# amplifier_v0003_-_1_Channel_Test.net
KiCad netlist of a schematic drawn in EAGLE
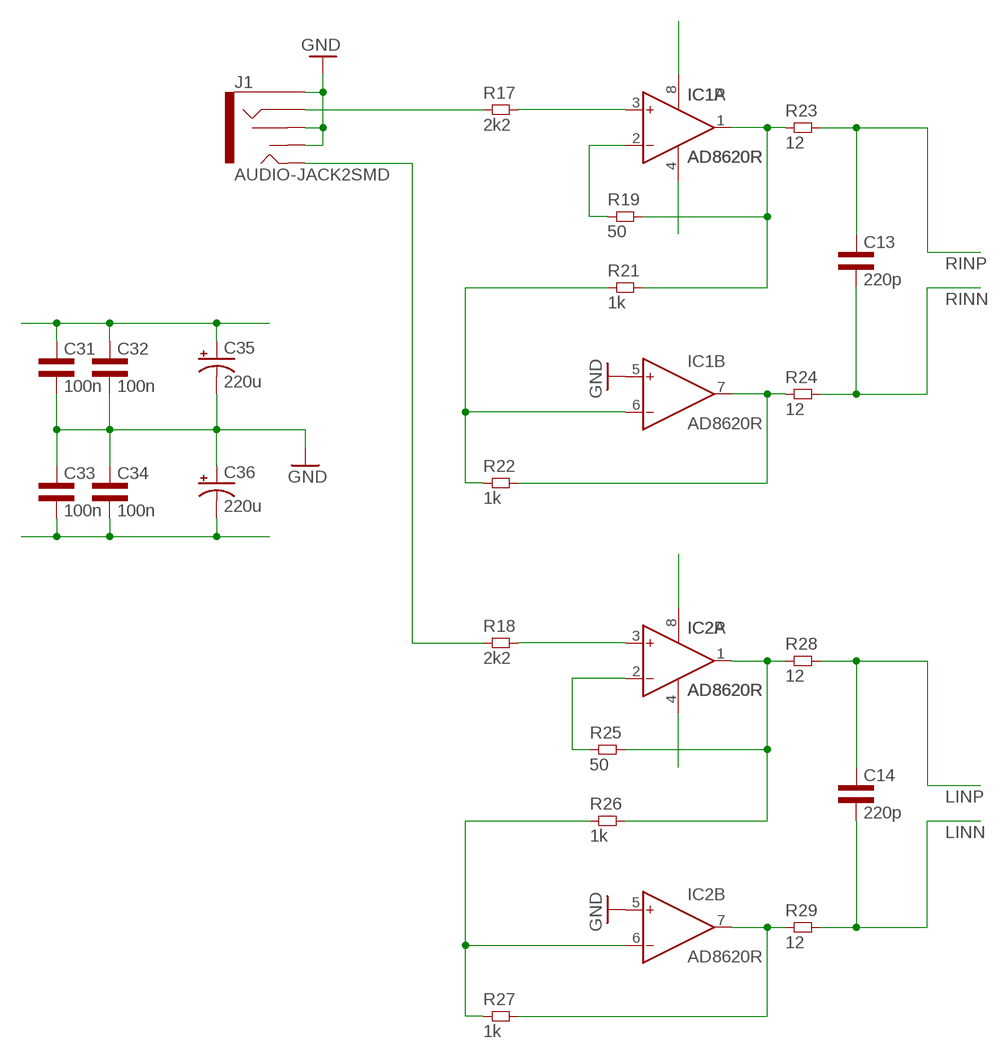
[diagram p0: schematic, sheet 1]
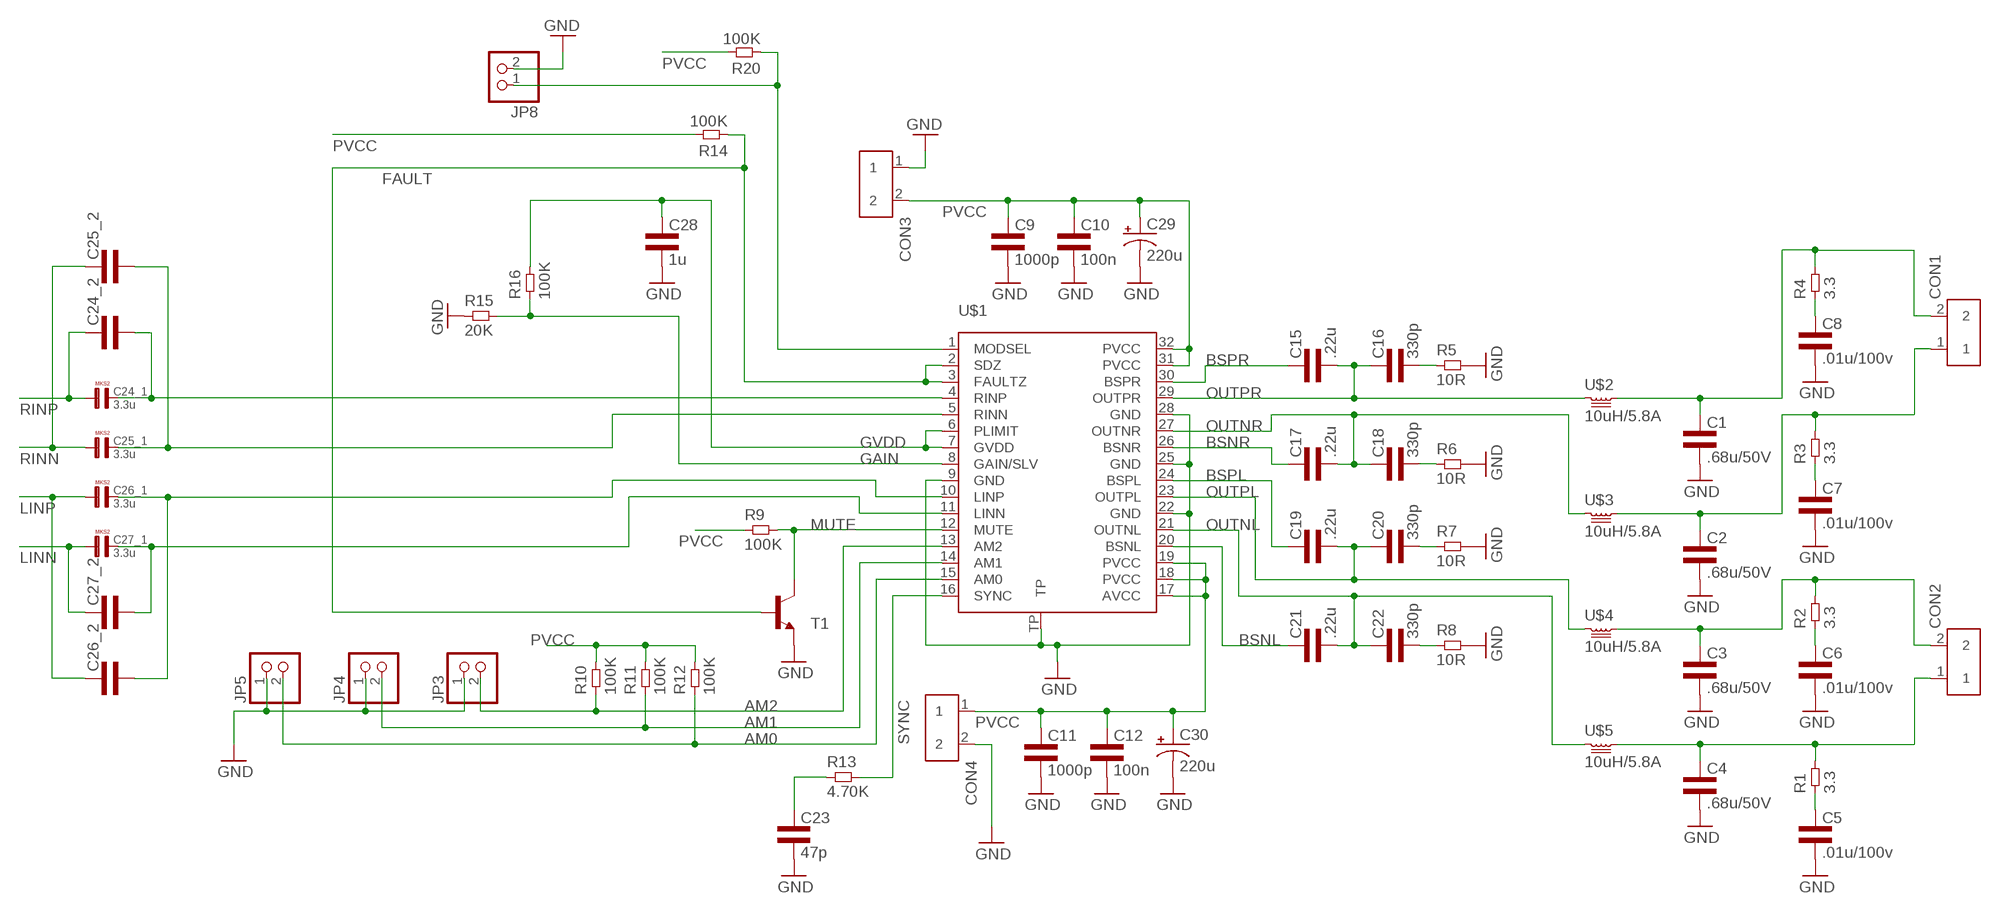
[diagram p1: schematic, sheet 2]

(export (version "E")
  (design (tool "Eeschema 10.0.6"))
  (components
    (comp (ref "C13")
      (value "220p")
      (footprint "eagle-import:0603L3")
      (libsource (lib "eagle-import") (part "CAP0603L3"))
    )
    (comp (ref "C14")
      (value "220p")
      (footprint "eagle-import:0603L3")
      (libsource (lib "eagle-import") (part "CAP0603L3"))
    )
    (comp (ref "C31")
      (value "100n")
      (footprint "eagle-import:0603L3")
      (libsource (lib "eagle-import") (part "CAP0603L3"))
    )
    (comp (ref "C32")
      (value "100n")
      (footprint "eagle-import:0603L3")
      (libsource (lib "eagle-import") (part "CAP0603L3"))
    )
    (comp (ref "C33")
      (value "100n")
      (footprint "eagle-import:0603L3")
      (libsource (lib "eagle-import") (part "CAP0603L3"))
    )
    (comp (ref "C34")
      (value "100n")
      (footprint "eagle-import:0603L3")
      (libsource (lib "eagle-import") (part "CAP0603L3"))
    )
    (comp (ref "C35")
      (value "220u")
      (footprint "eagle-import:CT7343")
      (libsource (lib "eagle-import") (part "CPOL-USCT7343"))
    )
    (comp (ref "C36")
      (value "220u")
      (footprint "eagle-import:CT7343")
      (libsource (lib "eagle-import") (part "CPOL-USCT7343"))
    )
    (comp (ref "IC1")
      (value "AD8620R")
      (footprint "eagle-import:SO8")
      (fields (field (name "MF") "ALTERA CORPORATION") (field (name "MPN") "AD8620ARZ"))
      (libsource (lib "eagle-import") (part "AD8620R"))
    )
    (comp (ref "IC2")
      (value "AD8620R")
      (footprint "eagle-import:SO8")
      (fields (field (name "MF") "ALTERA CORPORATION") (field (name "MPN") "AD8620ARZ"))
      (libsource (lib "eagle-import") (part "AD8620R"))
    )
    (comp (ref "J1")
      (value "AUDIO-JACK2SMD")
      (footprint "eagle-import:AUDIO-JACK-3.5MM-SMD")
      (libsource (lib "eagle-import") (part "AUDIO-JACK2SMD"))
    )
    (comp (ref "R17")
      (value "2k2")
      (footprint "eagle-import:0603L3")
      (libsource (lib "eagle-import") (part "RES0603L3"))
    )
    (comp (ref "R18")
      (value "2k2")
      (footprint "eagle-import:0603L3")
      (libsource (lib "eagle-import") (part "RES0603L3"))
    )
    (comp (ref "R19")
      (value "50")
      (footprint "eagle-import:0603L3")
      (libsource (lib "eagle-import") (part "RES0603L3"))
    )
    (comp (ref "R21")
      (value "1k")
      (footprint "eagle-import:0603L3")
      (libsource (lib "eagle-import") (part "RES0603L3"))
    )
    (comp (ref "R22")
      (value "1k")
      (footprint "eagle-import:0603L3")
      (libsource (lib "eagle-import") (part "RES0603L3"))
    )
    (comp (ref "R23")
      (value "12")
      (footprint "eagle-import:0603L3")
      (libsource (lib "eagle-import") (part "RES0603L3"))
    )
    (comp (ref "R24")
      (value "12")
      (footprint "eagle-import:0603L3")
      (libsource (lib "eagle-import") (part "RES0603L3"))
    )
    (comp (ref "R25")
      (value "50")
      (footprint "eagle-import:0603L3")
      (libsource (lib "eagle-import") (part "RES0603L3"))
    )
    (comp (ref "R26")
      (value "1k")
      (footprint "eagle-import:0603L3")
      (libsource (lib "eagle-import") (part "RES0603L3"))
    )
    (comp (ref "R27")
      (value "1k")
      (footprint "eagle-import:0603L3")
      (libsource (lib "eagle-import") (part "RES0603L3"))
    )
    (comp (ref "R28")
      (value "12")
      (footprint "eagle-import:0603L3")
      (libsource (lib "eagle-import") (part "RES0603L3"))
    )
    (comp (ref "R29")
      (value "12")
      (footprint "eagle-import:0603L3")
      (libsource (lib "eagle-import") (part "RES0603L3"))
    )
    (comp (ref "C1")
      (value ".68u/50V")
      (footprint "eagle-import:1206L3")
      (libsource (lib "eagle-import") (part "CAP1206L3"))
    )
    (comp (ref "C2")
      (value ".68u/50V")
      (footprint "eagle-import:1206L3")
      (libsource (lib "eagle-import") (part "CAP1206L3"))
    )
    (comp (ref "C3")
      (value ".68u/50V")
      (footprint "eagle-import:1206L3")
      (libsource (lib "eagle-import") (part "CAP1206L3"))
    )
    (comp (ref "C4")
      (value ".68u/50V")
      (footprint "eagle-import:1206L3")
      (libsource (lib "eagle-import") (part "CAP1206L3"))
    )
    (comp (ref "C5")
      (value ".01u/100v")
      (footprint "eagle-import:0805L3")
      (libsource (lib "eagle-import") (part "CAP0805L3"))
    )
    (comp (ref "C6")
      (value ".01u/100v")
      (footprint "eagle-import:0805L3")
      (libsource (lib "eagle-import") (part "CAP0805L3"))
    )
    (comp (ref "C7")
      (value ".01u/100v")
      (footprint "eagle-import:0805L3")
      (libsource (lib "eagle-import") (part "CAP0805L3"))
    )
    (comp (ref "C8")
      (value ".01u/100v")
      (footprint "eagle-import:0805L3")
      (libsource (lib "eagle-import") (part "CAP0805L3"))
    )
    (comp (ref "C9")
      (value "1000p")
      (footprint "eagle-import:0603L3")
      (libsource (lib "eagle-import") (part "CAP0603L3"))
    )
    (comp (ref "C10")
      (value "100n")
      (footprint "eagle-import:0603L3")
      (libsource (lib "eagle-import") (part "CAP0603L3"))
    )
    (comp (ref "C11")
      (value "1000p")
      (footprint "eagle-import:0603L3")
      (libsource (lib "eagle-import") (part "CAP0603L3"))
    )
    (comp (ref "C12")
      (value "100n")
      (footprint "eagle-import:0603L3")
      (libsource (lib "eagle-import") (part "CAP0603L3"))
    )
    (comp (ref "C15")
      (value ".22u")
      (footprint "eagle-import:0603L3")
      (libsource (lib "eagle-import") (part "CAP0603L3"))
    )
    (comp (ref "C16")
      (value "330p")
      (footprint "eagle-import:0603L3")
      (libsource (lib "eagle-import") (part "CAP0603L3"))
    )
    (comp (ref "C17")
      (value ".22u")
      (footprint "eagle-import:0603L3")
      (libsource (lib "eagle-import") (part "CAP0603L3"))
    )
    (comp (ref "C18")
      (value "330p")
      (footprint "eagle-import:0603L3")
      (libsource (lib "eagle-import") (part "CAP0603L3"))
    )
    (comp (ref "C19")
      (value ".22u")
      (footprint "eagle-import:0603L3")
      (libsource (lib "eagle-import") (part "CAP0603L3"))
    )
    (comp (ref "C20")
      (value "330p")
      (footprint "eagle-import:0603L3")
      (libsource (lib "eagle-import") (part "CAP0603L3"))
    )
    (comp (ref "C21")
      (value ".22u")
      (footprint "eagle-import:0603L3")
      (libsource (lib "eagle-import") (part "CAP0603L3"))
    )
    (comp (ref "C22")
      (value "330p")
      (footprint "eagle-import:0603L3")
      (libsource (lib "eagle-import") (part "CAP0603L3"))
    )
    (comp (ref "C23")
      (value "47p")
      (footprint "eagle-import:0603L3")
      (libsource (lib "eagle-import") (part "CAP0603L3"))
    )
    (comp (ref "C24_1")
      (value "3.3u")
      (footprint "eagle-import:R5B5K5")
      (libsource (lib "eagle-import") (part "3,3µF"))
    )
    (comp (ref "C24_2")
      (value "CAP1206L3")
      (footprint "eagle-import:1206L3")
      (libsource (lib "eagle-import") (part "CAP1206L3"))
    )
    (comp (ref "C25_1")
      (value "3.3u")
      (footprint "eagle-import:R5B5K5")
      (libsource (lib "eagle-import") (part "3,3µF"))
    )
    (comp (ref "C25_2")
      (value "CAP1206L3")
      (footprint "eagle-import:1206L3")
      (libsource (lib "eagle-import") (part "CAP1206L3"))
    )
    (comp (ref "C26_1")
      (value "3.3u")
      (footprint "eagle-import:R5B5K5")
      (libsource (lib "eagle-import") (part "3,3µF"))
    )
    (comp (ref "C26_2")
      (value "CAP1206L3")
      (footprint "eagle-import:1206L3")
      (libsource (lib "eagle-import") (part "CAP1206L3"))
    )
    (comp (ref "C27_1")
      (value "3.3u")
      (footprint "eagle-import:R5B5K5")
      (libsource (lib "eagle-import") (part "3,3µF"))
    )
    (comp (ref "C27_2")
      (value "CAP1206L3")
      (footprint "eagle-import:1206L3")
      (libsource (lib "eagle-import") (part "CAP1206L3"))
    )
    (comp (ref "C28")
      (value "1u")
      (footprint "eagle-import:0603L3")
      (libsource (lib "eagle-import") (part "CAP0603L3"))
    )
    (comp (ref "C29")
      (value "220u")
      (footprint "eagle-import:PANASONIC_G")
      (libsource (lib "eagle-import") (part "CPOL-USG"))
    )
    (comp (ref "C30")
      (value "220u")
      (footprint "eagle-import:PANASONIC_G")
      (libsource (lib "eagle-import") (part "CPOL-USG"))
    )
    (comp (ref "CON1")
      (value "TERM_BLOCK_2")
      (footprint "eagle-import:TERM_BLOCK_2")
      (libsource (lib "eagle-import") (part "TERM_BLOCK_2"))
    )
    (comp (ref "CON2")
      (value "TERM_BLOCK_2")
      (footprint "eagle-import:TERM_BLOCK_2")
      (libsource (lib "eagle-import") (part "TERM_BLOCK_2"))
    )
    (comp (ref "CON3")
      (value "TERM_BLOCK_2")
      (footprint "eagle-import:TERM_BLOCK_2")
      (libsource (lib "eagle-import") (part "TERM_BLOCK_2"))
    )
    (comp (ref "CON4")
      (value "TERM_BLOCK_2")
      (footprint "eagle-import:TERM_BLOCK_2")
      (libsource (lib "eagle-import") (part "TERM_BLOCK_2"))
    )
    (comp (ref "JP3")
      (value "PINHD-1X2")
      (footprint "eagle-import:1X02")
      (libsource (lib "eagle-import") (part "PINHD-1X2"))
    )
    (comp (ref "JP4")
      (value "PINHD-1X2")
      (footprint "eagle-import:1X02")
      (libsource (lib "eagle-import") (part "PINHD-1X2"))
    )
    (comp (ref "JP5")
      (value "PINHD-1X2")
      (footprint "eagle-import:1X02")
      (libsource (lib "eagle-import") (part "PINHD-1X2"))
    )
    (comp (ref "JP8")
      (value "PINHD-1X2")
      (footprint "eagle-import:1X02")
      (libsource (lib "eagle-import") (part "PINHD-1X2"))
    )
    (comp (ref "R1")
      (value "3.3")
      (footprint "eagle-import:0603L3")
      (libsource (lib "eagle-import") (part "RES0603L3"))
    )
    (comp (ref "R2")
      (value "3.3")
      (footprint "eagle-import:0603L3")
      (libsource (lib "eagle-import") (part "RES0603L3"))
    )
    (comp (ref "R3")
      (value "3.3")
      (footprint "eagle-import:0603L3")
      (libsource (lib "eagle-import") (part "RES0603L3"))
    )
    (comp (ref "R4")
      (value "3.3")
      (footprint "eagle-import:0603L3")
      (libsource (lib "eagle-import") (part "RES0603L3"))
    )
    (comp (ref "R5")
      (value "10R")
      (footprint "eagle-import:1206L3")
      (libsource (lib "eagle-import") (part "RES1206L3"))
    )
    (comp (ref "R6")
      (value "10R")
      (footprint "eagle-import:1206L3")
      (libsource (lib "eagle-import") (part "RES1206L3"))
    )
    (comp (ref "R7")
      (value "10R")
      (footprint "eagle-import:1206L3")
      (libsource (lib "eagle-import") (part "RES1206L3"))
    )
    (comp (ref "R8")
      (value "10R")
      (footprint "eagle-import:1206L3")
      (libsource (lib "eagle-import") (part "RES1206L3"))
    )
    (comp (ref "R9")
      (value "100K")
      (footprint "eagle-import:0603L3")
      (libsource (lib "eagle-import") (part "RES0603L3"))
    )
    (comp (ref "R10")
      (value "100K")
      (footprint "eagle-import:0603L3")
      (libsource (lib "eagle-import") (part "RES0603L3"))
    )
    (comp (ref "R11")
      (value "100K")
      (footprint "eagle-import:0603L3")
      (libsource (lib "eagle-import") (part "RES0603L3"))
    )
    (comp (ref "R12")
      (value "100K")
      (footprint "eagle-import:0603L3")
      (libsource (lib "eagle-import") (part "RES0603L3"))
    )
    (comp (ref "R13")
      (value "4.70K")
      (footprint "eagle-import:0603L3")
      (libsource (lib "eagle-import") (part "RES0603L3"))
    )
    (comp (ref "R14")
      (value "100K")
      (footprint "eagle-import:0603L3")
      (libsource (lib "eagle-import") (part "RES0603L3"))
    )
    (comp (ref "R15")
      (value "20K")
      (footprint "eagle-import:0603L3")
      (libsource (lib "eagle-import") (part "RES0603L3"))
    )
    (comp (ref "R16")
      (value "100K")
      (footprint "eagle-import:0603L3")
      (libsource (lib "eagle-import") (part "RES0603L3"))
    )
    (comp (ref "R20")
      (value "100K")
      (footprint "eagle-import:0603L3")
      (libsource (lib "eagle-import") (part "RES0603L3"))
    )
    (comp (ref "T1")
      (value "TRANSISTOR_MMBT2222ALT1-NPN-SOT23-BEC")
      (footprint "eagle-import:TRANSISTOR_SOT23-BEC")
      (libsource (lib "eagle-import") (part "TRANSISTOR_-NPN-SOT23-BECMMBT2222ALT1"))
    )
    (comp (ref "U$1")
      (value "TPA3116")
      (footprint "eagle-import:R-PDSO-32")
      (libsource (lib "eagle-import") (part "TPA3116"))
    )
    (comp (ref "U$2")
      (value "10uH/5.8A")
      (footprint "eagle-import:DR127")
      (libsource (lib "eagle-import") (part "INDUCTORDR127"))
    )
    (comp (ref "U$3")
      (value "10uH/5.8A")
      (footprint "eagle-import:DR127")
      (libsource (lib "eagle-import") (part "INDUCTORDR127"))
    )
    (comp (ref "U$4")
      (value "10uH/5.8A")
      (footprint "eagle-import:DR127")
      (libsource (lib "eagle-import") (part "INDUCTORDR127"))
    )
    (comp (ref "U$5")
      (value "10uH/5.8A")
      (footprint "eagle-import:DR127")
      (libsource (lib "eagle-import") (part "INDUCTORDR127"))
    )
  )
  (nets
    (net (code "1") (name "AM0") (class "Default")
      (node (ref "JP5") (pin "2") (pinfunction "2_2") (pintype "passive"))
      (node (ref "R12") (pin "P$1") (pinfunction "1_P$1") (pintype "bidirectional"))
      (node (ref "U$1") (pin "15") (pinfunction "AM0_15") (pintype "bidirectional"))
    )
    (net (code "2") (name "AM1") (class "Default")
      (node (ref "JP4") (pin "2") (pinfunction "2_2") (pintype "passive"))
      (node (ref "R11") (pin "P$1") (pinfunction "1_P$1") (pintype "bidirectional"))
      (node (ref "U$1") (pin "14") (pinfunction "AM1_14") (pintype "bidirectional"))
    )
    (net (code "3") (name "AM2") (class "Default")
      (node (ref "JP3") (pin "2") (pinfunction "2_2") (pintype "passive"))
      (node (ref "R10") (pin "P$1") (pinfunction "1_P$1") (pintype "bidirectional"))
      (node (ref "U$1") (pin "13") (pinfunction "AM2_13") (pintype "bidirectional"))
    )
    (net (code "4") (name "BSNL") (class "Default")
      (node (ref "C21") (pin "P$1") (pinfunction "1_P$1") (pintype "bidirectional"))
      (node (ref "U$1") (pin "20") (pinfunction "BSNL_20") (pintype "bidirectional"))
    )
    (net (code "5") (name "BSNR") (class "Default")
      (node (ref "C17") (pin "P$1") (pinfunction "1_P$1") (pintype "bidirectional"))
      (node (ref "U$1") (pin "26") (pinfunction "BSNR_26") (pintype "bidirectional"))
    )
    (net (code "6") (name "BSPL") (class "Default")
      (node (ref "C19") (pin "P$1") (pinfunction "1_P$1") (pintype "bidirectional"))
      (node (ref "U$1") (pin "24") (pinfunction "BSPL_24") (pintype "bidirectional"))
    )
    (net (code "7") (name "BSPR") (class "Default")
      (node (ref "C15") (pin "P$1") (pinfunction "1_P$1") (pintype "bidirectional"))
      (node (ref "U$1") (pin "30") (pinfunction "BSPR_30") (pintype "bidirectional"))
    )
    (net (code "8") (name "FAULT") (class "Default")
      (node (ref "R14") (pin "P$1") (pinfunction "1_P$1") (pintype "bidirectional"))
      (node (ref "T1") (pin "B") (pinfunction "B_B") (pintype "passive"))
      (node (ref "U$1") (pin "2") (pinfunction "SDZ_2") (pintype "bidirectional"))
      (node (ref "U$1") (pin "3") (pinfunction "FAULTZ_3") (pintype "bidirectional"))
    )
    (net (code "9") (name "GAIN") (class "Default")
      (node (ref "R15") (pin "P$2") (pinfunction "2_P$2") (pintype "bidirectional"))
      (node (ref "R16") (pin "P$1") (pinfunction "1_P$1") (pintype "bidirectional"))
      (node (ref "U$1") (pin "8") (pinfunction "GAIN/SLV_8") (pintype "bidirectional"))
    )
    (net (code "10") (name "GND") (class "Default")
      (node (ref "C1") (pin "2") (pinfunction "2_2") (pintype "bidirectional"))
      (node (ref "C10") (pin "P$2") (pinfunction "2_P$2") (pintype "bidirectional"))
      (node (ref "C11") (pin "P$2") (pinfunction "2_P$2") (pintype "bidirectional"))
      (node (ref "C12") (pin "P$2") (pinfunction "2_P$2") (pintype "bidirectional"))
      (node (ref "C2") (pin "2") (pinfunction "2_2") (pintype "bidirectional"))
      (node (ref "C23") (pin "P$2") (pinfunction "2_P$2") (pintype "bidirectional"))
      (node (ref "C28") (pin "P$2") (pinfunction "2_P$2") (pintype "bidirectional"))
      (node (ref "C29") (pin "-") (pinfunction "-_-") (pintype "passive"))
      (node (ref "C3") (pin "2") (pinfunction "2_2") (pintype "bidirectional"))
      (node (ref "C30") (pin "-") (pinfunction "-_-") (pintype "passive"))
      (node (ref "C31") (pin "P$2") (pinfunction "2_P$2") (pintype "bidirectional"))
      (node (ref "C32") (pin "P$2") (pinfunction "2_P$2") (pintype "bidirectional"))
      (node (ref "C33") (pin "P$1") (pinfunction "1_P$1") (pintype "bidirectional"))
      (node (ref "C34") (pin "P$1") (pinfunction "1_P$1") (pintype "bidirectional"))
      (node (ref "C35") (pin "-") (pinfunction "-_-") (pintype "passive"))
      (node (ref "C36") (pin "+") (pinfunction "+_+") (pintype "passive"))
      (node (ref "C4") (pin "2") (pinfunction "2_2") (pintype "bidirectional"))
      (node (ref "C5") (pin "2") (pinfunction "2_2") (pintype "bidirectional"))
      (node (ref "C6") (pin "2") (pinfunction "2_2") (pintype "bidirectional"))
      (node (ref "C7") (pin "2") (pinfunction "2_2") (pintype "bidirectional"))
      (node (ref "C8") (pin "2") (pinfunction "2_2") (pintype "bidirectional"))
      (node (ref "C9") (pin "P$2") (pinfunction "2_P$2") (pintype "bidirectional"))
      (node (ref "CON3") (pin "1") (pinfunction "1_1") (pintype "bidirectional"))
      (node (ref "CON4") (pin "2") (pinfunction "2_2") (pintype "bidirectional"))
      (node (ref "IC1") (pin "5") (pinfunction "IN+_5") (pintype "input"))
      (node (ref "IC2") (pin "5") (pinfunction "IN+_5") (pintype "input"))
      (node (ref "J1") (pin "RSH") (pinfunction "RSH_RSH") (pintype "bidirectional"))
      (node (ref "J1") (pin "SLEEVE") (pinfunction "SLEEVE_SLEEVE") (pintype "bidirectional"))
      (node (ref "J1") (pin "TSH") (pinfunction "TSH_TSH") (pintype "bidirectional"))
      (node (ref "JP3") (pin "1") (pinfunction "1_1") (pintype "passive"))
      (node (ref "JP4") (pin "1") (pinfunction "1_1") (pintype "passive"))
      (node (ref "JP5") (pin "1") (pinfunction "1_1") (pintype "passive"))
      (node (ref "JP8") (pin "2") (pinfunction "2_2") (pintype "passive"))
      (node (ref "R15") (pin "P$1") (pinfunction "1_P$1") (pintype "bidirectional"))
      (node (ref "R5") (pin "2") (pinfunction "2_2") (pintype "bidirectional"))
      (node (ref "R6") (pin "2") (pinfunction "2_2") (pintype "bidirectional"))
      (node (ref "R7") (pin "2") (pinfunction "2_2") (pintype "bidirectional"))
      (node (ref "R8") (pin "2") (pinfunction "2_2") (pintype "bidirectional"))
      (node (ref "T1") (pin "E") (pinfunction "E_E") (pintype "passive"))
      (node (ref "U$1") (pin "22") (pinfunction "GND_22") (pintype "bidirectional"))
      (node (ref "U$1") (pin "25") (pinfunction "GND_25") (pintype "bidirectional"))
      (node (ref "U$1") (pin "28") (pinfunction "GND_28") (pintype "bidirectional"))
      (node (ref "U$1") (pin "9") (pinfunction "GND_9") (pintype "bidirectional"))
      (node (ref "U$1") (pin "TP") (pinfunction "TP_TP") (pintype "bidirectional"))
    )
    (net (code "11") (name "GVDD") (class "Default")
      (node (ref "C28") (pin "P$1") (pinfunction "1_P$1") (pintype "bidirectional"))
      (node (ref "R16") (pin "P$2") (pinfunction "2_P$2") (pintype "bidirectional"))
      (node (ref "U$1") (pin "6") (pinfunction "PLIMIT_6") (pintype "bidirectional"))
      (node (ref "U$1") (pin "7") (pinfunction "GVDD_7") (pintype "bidirectional"))
    )
    (net (code "12") (name "LINN") (class "Default")
      (node (ref "C14") (pin "P$2") (pinfunction "2_P$2") (pintype "bidirectional"))
      (node (ref "C27_1") (pin "1") (pinfunction "1_1") (pintype "passive"))
      (node (ref "C27_2") (pin "1") (pinfunction "1_1") (pintype "bidirectional"))
      (node (ref "R29") (pin "P$2") (pinfunction "2_P$2") (pintype "bidirectional"))
    )
    (net (code "13") (name "LINP") (class "Default")
      (node (ref "C14") (pin "P$1") (pinfunction "1_P$1") (pintype "bidirectional"))
      (node (ref "C26_1") (pin "1") (pinfunction "1_1") (pintype "passive"))
      (node (ref "C26_2") (pin "1") (pinfunction "1_1") (pintype "bidirectional"))
      (node (ref "R28") (pin "P$2") (pinfunction "2_P$2") (pintype "bidirectional"))
    )
    (net (code "14") (name "MUTE") (class "Default")
      (node (ref "R9") (pin "P$2") (pinfunction "2_P$2") (pintype "bidirectional"))
      (node (ref "T1") (pin "C") (pinfunction "C_C") (pintype "passive"))
      (node (ref "U$1") (pin "12") (pinfunction "MUTE_12") (pintype "bidirectional"))
    )
    (net (code "15") (name "Net-(C16-2)") (class "Default")
      (node (ref "C16") (pin "P$2") (pinfunction "2_P$2") (pintype "bidirectional"))
      (node (ref "R5") (pin "1") (pinfunction "1_1") (pintype "bidirectional"))
    )
    (net (code "16") (name "Net-(C18-2)") (class "Default")
      (node (ref "C18") (pin "P$2") (pinfunction "2_P$2") (pintype "bidirectional"))
      (node (ref "R6") (pin "1") (pinfunction "1_1") (pintype "bidirectional"))
    )
    (net (code "17") (name "Net-(C20-2)") (class "Default")
      (node (ref "C20") (pin "P$2") (pinfunction "2_P$2") (pintype "bidirectional"))
      (node (ref "R7") (pin "1") (pinfunction "1_1") (pintype "bidirectional"))
    )
    (net (code "18") (name "Net-(C22-2)") (class "Default")
      (node (ref "C22") (pin "P$2") (pinfunction "2_P$2") (pintype "bidirectional"))
      (node (ref "R8") (pin "1") (pinfunction "1_1") (pintype "bidirectional"))
    )
    (net (code "19") (name "Net-(C23-1)") (class "Default")
      (node (ref "C23") (pin "P$1") (pinfunction "1_P$1") (pintype "bidirectional"))
      (node (ref "R13") (pin "P$1") (pinfunction "1_P$1") (pintype "bidirectional"))
    )
    (net (code "20") (name "Net-(IC1A-IN+)") (class "Default")
      (node (ref "IC1") (pin "3") (pinfunction "IN+_3") (pintype "input"))
      (node (ref "R17") (pin "P$2") (pinfunction "2_P$2") (pintype "bidirectional"))
    )
    (net (code "21") (name "Net-(IC1A-IN-)") (class "Default")
      (node (ref "IC1") (pin "2") (pinfunction "IN-_2") (pintype "input"))
      (node (ref "R19") (pin "P$1") (pinfunction "1_P$1") (pintype "bidirectional"))
    )
    (net (code "22") (name "Net-(IC1A-OUT)") (class "Default")
      (node (ref "IC1") (pin "1") (pinfunction "OUT_1") (pintype "output"))
      (node (ref "R19") (pin "P$2") (pinfunction "2_P$2") (pintype "bidirectional"))
      (node (ref "R21") (pin "P$2") (pinfunction "2_P$2") (pintype "bidirectional"))
      (node (ref "R23") (pin "P$1") (pinfunction "1_P$1") (pintype "bidirectional"))
    )
    (net (code "23") (name "Net-(IC1B-IN-)") (class "Default")
      (node (ref "IC1") (pin "6") (pinfunction "IN-_6") (pintype "input"))
      (node (ref "R21") (pin "P$1") (pinfunction "1_P$1") (pintype "bidirectional"))
      (node (ref "R22") (pin "P$1") (pinfunction "1_P$1") (pintype "bidirectional"))
    )
    (net (code "24") (name "Net-(IC1B-OUT)") (class "Default")
      (node (ref "IC1") (pin "7") (pinfunction "OUT_7") (pintype "output"))
      (node (ref "R22") (pin "P$2") (pinfunction "2_P$2") (pintype "bidirectional"))
      (node (ref "R24") (pin "P$1") (pinfunction "1_P$1") (pintype "bidirectional"))
    )
    (net (code "25") (name "Net-(IC2A-IN+)") (class "Default")
      (node (ref "IC2") (pin "3") (pinfunction "IN+_3") (pintype "input"))
      (node (ref "R18") (pin "P$2") (pinfunction "2_P$2") (pintype "bidirectional"))
    )
    (net (code "26") (name "Net-(IC2A-IN-)") (class "Default")
      (node (ref "IC2") (pin "2") (pinfunction "IN-_2") (pintype "input"))
      (node (ref "R25") (pin "P$1") (pinfunction "1_P$1") (pintype "bidirectional"))
    )
    (net (code "27") (name "Net-(IC2A-OUT)") (class "Default")
      (node (ref "IC2") (pin "1") (pinfunction "OUT_1") (pintype "output"))
      (node (ref "R25") (pin "P$2") (pinfunction "2_P$2") (pintype "bidirectional"))
      (node (ref "R26") (pin "P$2") (pinfunction "2_P$2") (pintype "bidirectional"))
      (node (ref "R28") (pin "P$1") (pinfunction "1_P$1") (pintype "bidirectional"))
    )
    (net (code "28") (name "Net-(IC2B-IN-)") (class "Default")
      (node (ref "IC2") (pin "6") (pinfunction "IN-_6") (pintype "input"))
      (node (ref "R26") (pin "P$1") (pinfunction "1_P$1") (pintype "bidirectional"))
      (node (ref "R27") (pin "P$1") (pinfunction "1_P$1") (pintype "bidirectional"))
    )
    (net (code "29") (name "Net-(IC2B-OUT)") (class "Default")
      (node (ref "IC2") (pin "7") (pinfunction "OUT_7") (pintype "output"))
      (node (ref "R27") (pin "P$2") (pinfunction "2_P$2") (pintype "bidirectional"))
      (node (ref "R29") (pin "P$1") (pinfunction "1_P$1") (pintype "bidirectional"))
    )
    (net (code "30") (name "Net-(R1-1)") (class "Default")
      (node (ref "C5") (pin "1") (pinfunction "1_1") (pintype "bidirectional"))
      (node (ref "R1") (pin "P$1") (pinfunction "1_P$1") (pintype "bidirectional"))
    )
    (net (code "31") (name "Net-(R1-2)") (class "Default")
      (node (ref "C4") (pin "1") (pinfunction "1_1") (pintype "bidirectional"))
      (node (ref "CON2") (pin "1") (pinfunction "1_1") (pintype "bidirectional"))
      (node (ref "R1") (pin "P$2") (pinfunction "2_P$2") (pintype "bidirectional"))
      (node (ref "U$5") (pin "2") (pinfunction "2_2") (pintype "bidirectional"))
    )
    (net (code "32") (name "Net-(R2-1)") (class "Default")
      (node (ref "C6") (pin "1") (pinfunction "1_1") (pintype "bidirectional"))
      (node (ref "R2") (pin "P$1") (pinfunction "1_P$1") (pintype "bidirectional"))
    )
    (net (code "33") (name "Net-(R2-2)") (class "Default")
      (node (ref "C3") (pin "1") (pinfunction "1_1") (pintype "bidirectional"))
      (node (ref "CON2") (pin "2") (pinfunction "2_2") (pintype "bidirectional"))
      (node (ref "R2") (pin "P$2") (pinfunction "2_P$2") (pintype "bidirectional"))
      (node (ref "U$4") (pin "2") (pinfunction "2_2") (pintype "bidirectional"))
    )
    (net (code "34") (name "Net-(R3-1)") (class "Default")
      (node (ref "C7") (pin "1") (pinfunction "1_1") (pintype "bidirectional"))
      (node (ref "R3") (pin "P$1") (pinfunction "1_P$1") (pintype "bidirectional"))
    )
    (net (code "35") (name "Net-(R3-2)") (class "Default")
      (node (ref "C2") (pin "1") (pinfunction "1_1") (pintype "bidirectional"))
      (node (ref "CON1") (pin "1") (pinfunction "1_1") (pintype "bidirectional"))
      (node (ref "R3") (pin "P$2") (pinfunction "2_P$2") (pintype "bidirectional"))
      (node (ref "U$3") (pin "2") (pinfunction "2_2") (pintype "bidirectional"))
    )
    (net (code "36") (name "Net-(R4-1)") (class "Default")
      (node (ref "C8") (pin "1") (pinfunction "1_1") (pintype "bidirectional"))
      (node (ref "R4") (pin "P$1") (pinfunction "1_P$1") (pintype "bidirectional"))
    )
    (net (code "37") (name "Net-(R4-2)") (class "Default")
      (node (ref "C1") (pin "1") (pinfunction "1_1") (pintype "bidirectional"))
      (node (ref "CON1") (pin "2") (pinfunction "2_2") (pintype "bidirectional"))
      (node (ref "R4") (pin "P$2") (pinfunction "2_P$2") (pintype "bidirectional"))
      (node (ref "U$2") (pin "2") (pinfunction "2_2") (pintype "bidirectional"))
    )
    (net (code "38") (name "Net-(R17-1)") (class "Default")
      (node (ref "J1") (pin "RING") (pinfunction "RING_RING") (pintype "bidirectional"))
      (node (ref "R17") (pin "P$1") (pinfunction "1_P$1") (pintype "bidirectional"))
    )
    (net (code "39") (name "Net-(R18-1)") (class "Default")
      (node (ref "J1") (pin "TIP") (pinfunction "TIP_TIP") (pintype "bidirectional"))
      (node (ref "R18") (pin "P$1") (pinfunction "1_P$1") (pintype "bidirectional"))
    )
    (net (code "40") (name "Net-(R20-1)") (class "Default")
      (node (ref "JP8") (pin "1") (pinfunction "1_1") (pintype "passive"))
      (node (ref "R20") (pin "P$1") (pinfunction "1_P$1") (pintype "bidirectional"))
      (node (ref "U$1") (pin "1") (pinfunction "MODSEL_1") (pintype "bidirectional"))
    )
    (net (code "41") (name "Net-(U$1-LINN)") (class "Default")
      (node (ref "C27_1") (pin "2") (pinfunction "2_2") (pintype "passive"))
      (node (ref "C27_2") (pin "2") (pinfunction "2_2") (pintype "bidirectional"))
      (node (ref "U$1") (pin "11") (pinfunction "LINN_11") (pintype "bidirectional"))
    )
    (net (code "42") (name "Net-(U$1-LINP)") (class "Default")
      (node (ref "C26_1") (pin "2") (pinfunction "2_2") (pintype "passive"))
      (node (ref "C26_2") (pin "2") (pinfunction "2_2") (pintype "bidirectional"))
      (node (ref "U$1") (pin "10") (pinfunction "LINP_10") (pintype "bidirectional"))
    )
    (net (code "43") (name "Net-(U$1-RINN)") (class "Default")
      (node (ref "C25_1") (pin "2") (pinfunction "2_2") (pintype "passive"))
      (node (ref "C25_2") (pin "2") (pinfunction "2_2") (pintype "bidirectional"))
      (node (ref "U$1") (pin "5") (pinfunction "RINN_5") (pintype "bidirectional"))
    )
    (net (code "44") (name "Net-(U$1-RINP)") (class "Default")
      (node (ref "C24_1") (pin "2") (pinfunction "2_2") (pintype "passive"))
      (node (ref "C24_2") (pin "2") (pinfunction "2_2") (pintype "bidirectional"))
      (node (ref "U$1") (pin "4") (pinfunction "RINP_4") (pintype "bidirectional"))
    )
    (net (code "45") (name "OUTNL") (class "Default")
      (node (ref "C21") (pin "P$2") (pinfunction "2_P$2") (pintype "bidirectional"))
      (node (ref "C22") (pin "P$1") (pinfunction "1_P$1") (pintype "bidirectional"))
      (node (ref "U$1") (pin "21") (pinfunction "OUTNL_21") (pintype "bidirectional"))
      (node (ref "U$5") (pin "1") (pinfunction "1_1") (pintype "bidirectional"))
    )
    (net (code "46") (name "OUTNR") (class "Default")
      (node (ref "C17") (pin "P$2") (pinfunction "2_P$2") (pintype "bidirectional"))
      (node (ref "C18") (pin "P$1") (pinfunction "1_P$1") (pintype "bidirectional"))
      (node (ref "U$1") (pin "27") (pinfunction "OUTNR_27") (pintype "bidirectional"))
      (node (ref "U$3") (pin "1") (pinfunction "1_1") (pintype "bidirectional"))
    )
    (net (code "47") (name "OUTPL") (class "Default")
      (node (ref "C19") (pin "P$2") (pinfunction "2_P$2") (pintype "bidirectional"))
      (node (ref "C20") (pin "P$1") (pinfunction "1_P$1") (pintype "bidirectional"))
      (node (ref "U$1") (pin "23") (pinfunction "OUTPL_23") (pintype "bidirectional"))
      (node (ref "U$4") (pin "1") (pinfunction "1_1") (pintype "bidirectional"))
    )
    (net (code "48") (name "OUTPR") (class "Default")
      (node (ref "C15") (pin "P$2") (pinfunction "2_P$2") (pintype "bidirectional"))
      (node (ref "C16") (pin "P$1") (pinfunction "1_P$1") (pintype "bidirectional"))
      (node (ref "U$1") (pin "29") (pinfunction "OUTPR_29") (pintype "bidirectional"))
      (node (ref "U$2") (pin "1") (pinfunction "1_1") (pintype "bidirectional"))
    )
    (net (code "49") (name "PVCC") (class "Default")
      (node (ref "C10") (pin "P$1") (pinfunction "1_P$1") (pintype "bidirectional"))
      (node (ref "C11") (pin "P$1") (pinfunction "1_P$1") (pintype "bidirectional"))
      (node (ref "C12") (pin "P$1") (pinfunction "1_P$1") (pintype "bidirectional"))
      (node (ref "C29") (pin "+") (pinfunction "+_+") (pintype "passive"))
      (node (ref "C30") (pin "+") (pinfunction "+_+") (pintype "passive"))
      (node (ref "C9") (pin "P$1") (pinfunction "1_P$1") (pintype "bidirectional"))
      (node (ref "CON3") (pin "2") (pinfunction "2_2") (pintype "bidirectional"))
      (node (ref "CON4") (pin "1") (pinfunction "1_1") (pintype "bidirectional"))
      (node (ref "R10") (pin "P$2") (pinfunction "2_P$2") (pintype "bidirectional"))
      (node (ref "R11") (pin "P$2") (pinfunction "2_P$2") (pintype "bidirectional"))
      (node (ref "R12") (pin "P$2") (pinfunction "2_P$2") (pintype "bidirectional"))
      (node (ref "R14") (pin "P$2") (pinfunction "2_P$2") (pintype "bidirectional"))
      (node (ref "R20") (pin "P$2") (pinfunction "2_P$2") (pintype "bidirectional"))
      (node (ref "R9") (pin "P$1") (pinfunction "1_P$1") (pintype "bidirectional"))
      (node (ref "U$1") (pin "17") (pinfunction "AVCC_17") (pintype "bidirectional"))
      (node (ref "U$1") (pin "18") (pinfunction "PVCC_18") (pintype "bidirectional"))
      (node (ref "U$1") (pin "19") (pinfunction "PVCC_19") (pintype "bidirectional"))
      (node (ref "U$1") (pin "31") (pinfunction "PVCC_31") (pintype "bidirectional"))
      (node (ref "U$1") (pin "32") (pinfunction "PVCC_32") (pintype "bidirectional"))
    )
    (net (code "50") (name "RINN") (class "Default")
      (node (ref "C13") (pin "P$2") (pinfunction "2_P$2") (pintype "bidirectional"))
      (node (ref "C25_1") (pin "1") (pinfunction "1_1") (pintype "passive"))
      (node (ref "C25_2") (pin "1") (pinfunction "1_1") (pintype "bidirectional"))
      (node (ref "R24") (pin "P$2") (pinfunction "2_P$2") (pintype "bidirectional"))
    )
    (net (code "51") (name "RINP") (class "Default")
      (node (ref "C13") (pin "P$1") (pinfunction "1_P$1") (pintype "bidirectional"))
      (node (ref "C24_1") (pin "1") (pinfunction "1_1") (pintype "passive"))
      (node (ref "C24_2") (pin "1") (pinfunction "1_1") (pintype "bidirectional"))
      (node (ref "R23") (pin "P$2") (pinfunction "2_P$2") (pintype "bidirectional"))
    )
    (net (code "52") (name "SYNC") (class "Default")
      (node (ref "R13") (pin "P$2") (pinfunction "2_P$2") (pintype "bidirectional"))
      (node (ref "U$1") (pin "16") (pinfunction "SYNC_16") (pintype "bidirectional"))
    )
    (net (code "53") (name "V+") (class "Default")
      (node (ref "C31") (pin "P$1") (pinfunction "1_P$1") (pintype "bidirectional"))
      (node (ref "C32") (pin "P$1") (pinfunction "1_P$1") (pintype "bidirectional"))
      (node (ref "C35") (pin "+") (pinfunction "+_+") (pintype "passive"))
      (node (ref "IC1") (pin "8") (pinfunction "V+_8") (pintype "power_in"))
      (node (ref "IC2") (pin "8") (pinfunction "V+_8") (pintype "power_in"))
    )
    (net (code "54") (name "V-") (class "Default")
      (node (ref "C33") (pin "P$2") (pinfunction "2_P$2") (pintype "bidirectional"))
      (node (ref "C34") (pin "P$2") (pinfunction "2_P$2") (pintype "bidirectional"))
      (node (ref "C36") (pin "-") (pinfunction "-_-") (pintype "passive"))
      (node (ref "IC1") (pin "4") (pinfunction "V-_4") (pintype "power_in"))
      (node (ref "IC2") (pin "4") (pinfunction "V-_4") (pintype "power_in"))
    )
  )
)
